# H_bridge.net
KiCad netlist of a schematic drawn in Altium Designer
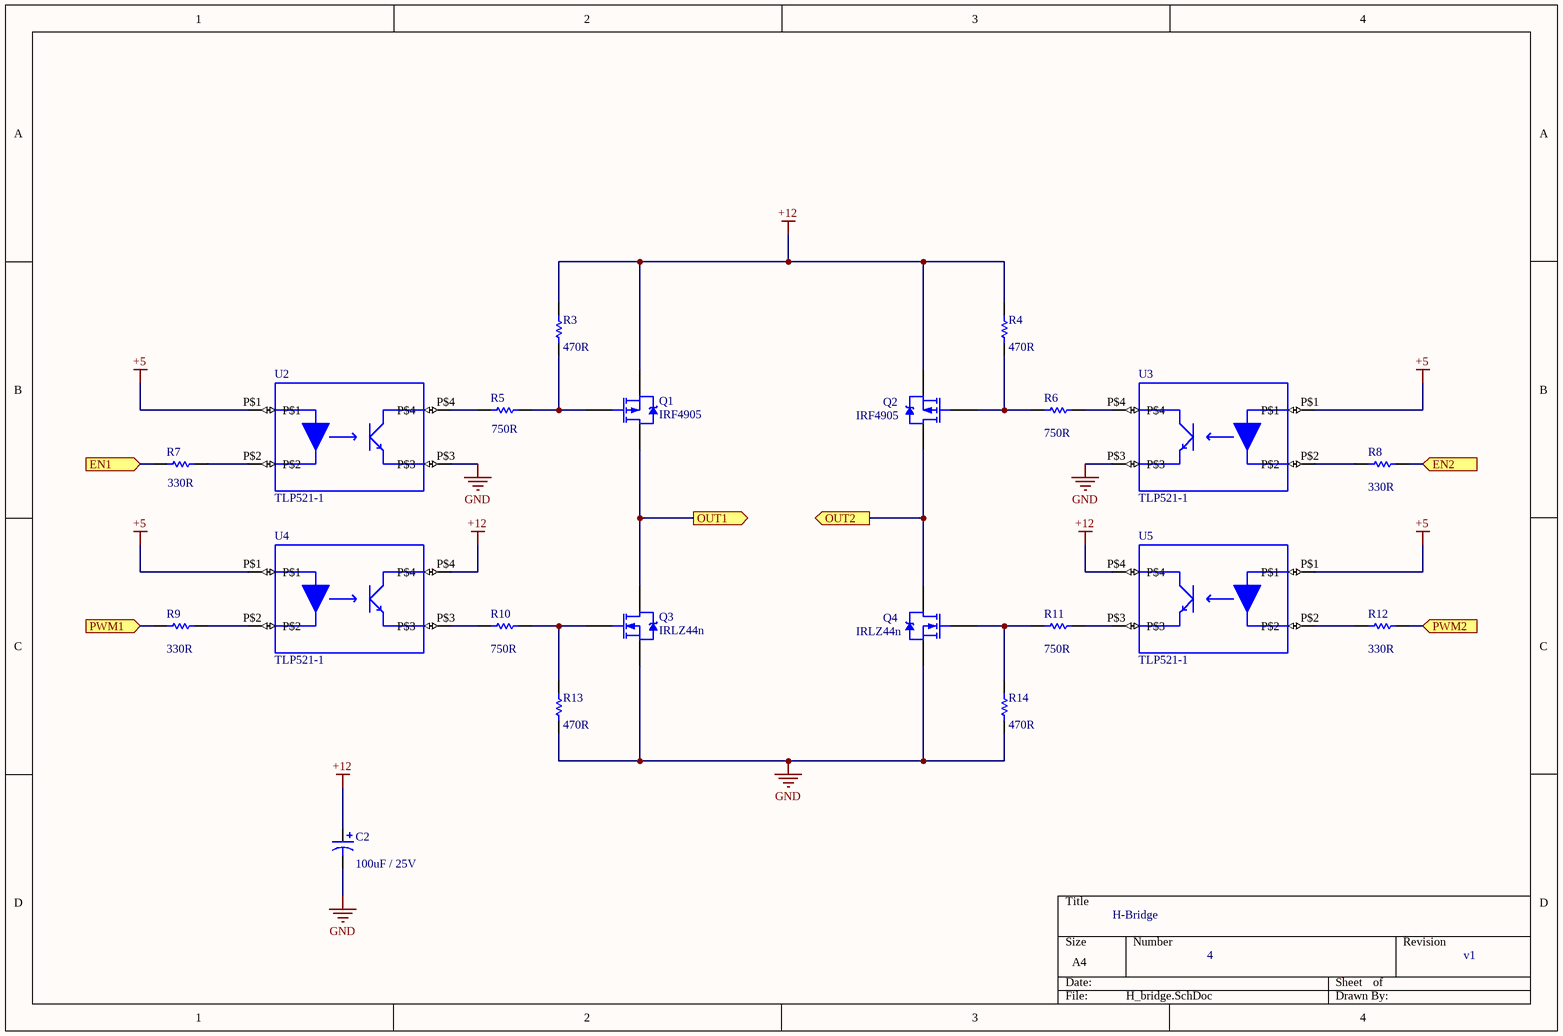
[diagram p0: H_bridge.SchDoc]

(export (version "E")
  (design (tool "Eeschema 10.0.6"))
  (components
    (comp (ref "C2")
      (value "100uF / 25V")
      (footprint "RB7.6-15")
      (description "Polarized Capacitor (Radial)")
      (fields (field (name "Comment") "Cap Pol1") (field (name "PUBLISHER") "Altium Limited"))
      (libsource (lib "Miscellaneous Devices") (part "Cap Pol1"))
    )
    (comp (ref "Q1")
      (value "IRF4905")
      (footprint "TO-220AB")
      (description "P-Channel Power MOSFET")
      (fields (field (name "PUBLISHER") "Altium Limited"))
      (libsource (lib "Miscellaneous Devices") (part "PMOS-2"))
    )
    (comp (ref "Q2")
      (value "IRF4905")
      (footprint "TO-220AB")
      (description "P-Channel Power MOSFET")
      (fields (field (name "PUBLISHER") "Altium Limited"))
      (libsource (lib "Miscellaneous Devices") (part "PMOS-2"))
    )
    (comp (ref "Q3")
      (value "IRLZ44n")
      (footprint "TO-220AB")
      (description "N-Channel Power MOSFET")
      (fields (field (name "PUBLISHER") "Altium Limited"))
      (libsource (lib "Miscellaneous Devices") (part "NMOS-2"))
    )
    (comp (ref "Q4")
      (value "IRLZ44n")
      (footprint "TO-220AB")
      (description "N-Channel Power MOSFET")
      (fields (field (name "PUBLISHER") "Altium Limited"))
      (libsource (lib "Miscellaneous Devices") (part "NMOS-2"))
    )
    (comp (ref "R3")
      (value "470R")
      (footprint "AXIAL-0.3")
      (description "Resistor")
      (fields (field (name "Comment") "Res1") (field (name "PUBLISHER") "Altium Limited"))
      (libsource (lib "Miscellaneous Devices") (part "Res1"))
    )
    (comp (ref "R4")
      (value "470R")
      (footprint "AXIAL-0.3")
      (description "Resistor")
      (fields (field (name "Comment") "Res1") (field (name "PUBLISHER") "Altium Limited"))
      (libsource (lib "Miscellaneous Devices") (part "Res1"))
    )
    (comp (ref "R5")
      (value "750R")
      (footprint "AXIAL-0.3")
      (description "Resistor")
      (fields (field (name "Comment") "Res1") (field (name "PUBLISHER") "Altium Limited"))
      (libsource (lib "Miscellaneous Devices") (part "Res1"))
    )
    (comp (ref "R6")
      (value "750R")
      (footprint "AXIAL-0.3")
      (description "Resistor")
      (fields (field (name "Comment") "Res1") (field (name "PUBLISHER") "Altium Limited"))
      (libsource (lib "Miscellaneous Devices") (part "Res1"))
    )
    (comp (ref "R7")
      (value "330R")
      (footprint "AXIAL-0.3")
      (description "Resistor")
      (fields (field (name "Comment") "Res1") (field (name "PUBLISHER") "Altium Limited"))
      (libsource (lib "Miscellaneous Devices") (part "Res1"))
    )
    (comp (ref "R8")
      (value "330R")
      (footprint "AXIAL-0.3")
      (description "Resistor")
      (fields (field (name "Comment") "Res1") (field (name "PUBLISHER") "Altium Limited"))
      (libsource (lib "Miscellaneous Devices") (part "Res1"))
    )
    (comp (ref "R9")
      (value "330R")
      (footprint "AXIAL-0.3")
      (description "Resistor")
      (fields (field (name "Comment") "Res1") (field (name "PUBLISHER") "Altium Limited"))
      (libsource (lib "Miscellaneous Devices") (part "Res1"))
    )
    (comp (ref "R10")
      (value "750R")
      (footprint "AXIAL-0.3")
      (description "Resistor")
      (fields (field (name "Comment") "Res1") (field (name "PUBLISHER") "Altium Limited"))
      (libsource (lib "Miscellaneous Devices") (part "Res1"))
    )
    (comp (ref "R11")
      (value "750R")
      (footprint "AXIAL-0.3")
      (description "Resistor")
      (fields (field (name "Comment") "Res1") (field (name "PUBLISHER") "Altium Limited"))
      (libsource (lib "Miscellaneous Devices") (part "Res1"))
    )
    (comp (ref "R12")
      (value "330R")
      (footprint "AXIAL-0.3")
      (description "Resistor")
      (fields (field (name "Comment") "Res1") (field (name "PUBLISHER") "Altium Limited"))
      (libsource (lib "Miscellaneous Devices") (part "Res1"))
    )
    (comp (ref "R13")
      (value "470R")
      (footprint "AXIAL-0.3")
      (description "Resistor")
      (fields (field (name "Comment") "Res1") (field (name "PUBLISHER") "Altium Limited"))
      (libsource (lib "Miscellaneous Devices") (part "Res1"))
    )
    (comp (ref "R14")
      (value "470R")
      (footprint "AXIAL-0.3")
      (description "Resistor")
      (fields (field (name "Comment") "Res1") (field (name "PUBLISHER") "Altium Limited"))
      (libsource (lib "Miscellaneous Devices") (part "Res1"))
    )
    (comp (ref "U2")
      (value "TLP521-1")
      (footprint "TLP521-1")
      (description "ICM006")
      (fields (field (name "MF") "Isocom"))
      (libsource (lib "TLP521-1") (part "TLP521-1"))
    )
    (comp (ref "U3")
      (value "TLP521-1")
      (footprint "TLP521-1")
      (description "ICM006")
      (fields (field (name "MF") "Isocom"))
      (libsource (lib "TLP521-1") (part "TLP521-1"))
    )
    (comp (ref "U4")
      (value "TLP521-1")
      (footprint "TLP521-1")
      (description "ICM006")
      (fields (field (name "MF") "Isocom"))
      (libsource (lib "TLP521-1") (part "TLP521-1"))
    )
    (comp (ref "U5")
      (value "TLP521-1")
      (footprint "TLP521-1")
      (description "ICM006")
      (fields (field (name "MF") "Isocom"))
      (libsource (lib "TLP521-1") (part "TLP521-1"))
    )
  )
  (nets
    (net (code "1") (name "+5") (class "Default")
      (node (ref "U2") (pin "P$1") (pinfunction "P$1_P$1") (pintype "bidirectional"))
      (node (ref "U3") (pin "P$1") (pinfunction "P$1_P$1") (pintype "bidirectional"))
      (node (ref "U4") (pin "P$1") (pinfunction "P$1_P$1") (pintype "bidirectional"))
      (node (ref "U5") (pin "P$1") (pinfunction "P$1_P$1") (pintype "bidirectional"))
    )
    (net (code "2") (name "+12") (class "Default")
      (node (ref "C2") (pin "1") (pinfunction "1_1") (pintype "passive"))
      (node (ref "Q1") (pin "3") (pinfunction "S_3") (pintype "passive"))
      (node (ref "Q2") (pin "3") (pinfunction "S_3") (pintype "passive"))
      (node (ref "R3") (pin "2") (pinfunction "2_2") (pintype "passive"))
      (node (ref "R4") (pin "2") (pinfunction "2_2") (pintype "passive"))
      (node (ref "U4") (pin "P$4") (pinfunction "P$4_P$4") (pintype "bidirectional"))
      (node (ref "U5") (pin "P$4") (pinfunction "P$4_P$4") (pintype "bidirectional"))
    )
    (net (code "3") (name "/EN1") (class "Default")
      (node (ref "R7") (pin "1") (pinfunction "1_1") (pintype "passive"))
    )
    (net (code "4") (name "/EN2") (class "Default")
      (node (ref "R8") (pin "1") (pinfunction "1_1") (pintype "passive"))
    )
    (net (code "5") (name "/OUT1") (class "Default")
      (node (ref "Q1") (pin "2") (pinfunction "D_2") (pintype "passive"))
      (node (ref "Q3") (pin "2") (pinfunction "D_2") (pintype "passive"))
    )
    (net (code "6") (name "/OUT2") (class "Default")
      (node (ref "Q2") (pin "2") (pinfunction "D_2") (pintype "passive"))
      (node (ref "Q4") (pin "2") (pinfunction "D_2") (pintype "passive"))
    )
    (net (code "7") (name "/PWM1") (class "Default")
      (node (ref "R9") (pin "2") (pinfunction "2_2") (pintype "passive"))
    )
    (net (code "8") (name "/PWM2") (class "Default")
      (node (ref "R12") (pin "2") (pinfunction "2_2") (pintype "passive"))
    )
    (net (code "9") (name "GND") (class "Default")
      (node (ref "C2") (pin "2") (pinfunction "2_2") (pintype "passive"))
      (node (ref "Q3") (pin "3") (pinfunction "S_3") (pintype "passive"))
      (node (ref "Q4") (pin "3") (pinfunction "S_3") (pintype "passive"))
      (node (ref "R13") (pin "2") (pinfunction "2_2") (pintype "passive"))
      (node (ref "R14") (pin "2") (pinfunction "2_2") (pintype "passive"))
      (node (ref "U2") (pin "P$3") (pinfunction "P$3_P$3") (pintype "bidirectional"))
      (node (ref "U3") (pin "P$3") (pinfunction "P$3_P$3") (pintype "bidirectional"))
    )
    (net (code "10") (name "Net-(Q1-G)") (class "Default")
      (node (ref "Q1") (pin "1") (pinfunction "G_1") (pintype "passive"))
      (node (ref "R3") (pin "1") (pinfunction "1_1") (pintype "passive"))
      (node (ref "R5") (pin "2") (pinfunction "2_2") (pintype "passive"))
    )
    (net (code "11") (name "Net-(Q2-G)") (class "Default")
      (node (ref "Q2") (pin "1") (pinfunction "G_1") (pintype "passive"))
      (node (ref "R4") (pin "1") (pinfunction "1_1") (pintype "passive"))
      (node (ref "R6") (pin "2") (pinfunction "2_2") (pintype "passive"))
    )
    (net (code "12") (name "Net-(Q3-G)") (class "Default")
      (node (ref "Q3") (pin "1") (pinfunction "G_1") (pintype "passive"))
      (node (ref "R10") (pin "1") (pinfunction "1_1") (pintype "passive"))
      (node (ref "R13") (pin "1") (pinfunction "1_1") (pintype "passive"))
    )
    (net (code "13") (name "Net-(Q4-G)") (class "Default")
      (node (ref "Q4") (pin "1") (pinfunction "G_1") (pintype "passive"))
      (node (ref "R11") (pin "1") (pinfunction "1_1") (pintype "passive"))
      (node (ref "R14") (pin "1") (pinfunction "1_1") (pintype "passive"))
    )
    (net (code "14") (name "Net-(R5-Pad1)") (class "Default")
      (node (ref "R5") (pin "1") (pinfunction "1_1") (pintype "passive"))
      (node (ref "U2") (pin "P$4") (pinfunction "P$4_P$4") (pintype "bidirectional"))
    )
    (net (code "15") (name "Net-(R6-Pad1)") (class "Default")
      (node (ref "R6") (pin "1") (pinfunction "1_1") (pintype "passive"))
      (node (ref "U3") (pin "P$4") (pinfunction "P$4_P$4") (pintype "bidirectional"))
    )
    (net (code "16") (name "Net-(R7-Pad2)") (class "Default")
      (node (ref "R7") (pin "2") (pinfunction "2_2") (pintype "passive"))
      (node (ref "U2") (pin "P$2") (pinfunction "P$2_P$2") (pintype "bidirectional"))
    )
    (net (code "17") (name "Net-(R8-Pad2)") (class "Default")
      (node (ref "R8") (pin "2") (pinfunction "2_2") (pintype "passive"))
      (node (ref "U3") (pin "P$2") (pinfunction "P$2_P$2") (pintype "bidirectional"))
    )
    (net (code "18") (name "Net-(R9-Pad1)") (class "Default")
      (node (ref "R9") (pin "1") (pinfunction "1_1") (pintype "passive"))
      (node (ref "U4") (pin "P$2") (pinfunction "P$2_P$2") (pintype "bidirectional"))
    )
    (net (code "19") (name "Net-(R10-Pad2)") (class "Default")
      (node (ref "R10") (pin "2") (pinfunction "2_2") (pintype "passive"))
      (node (ref "U4") (pin "P$3") (pinfunction "P$3_P$3") (pintype "bidirectional"))
    )
    (net (code "20") (name "Net-(R11-Pad2)") (class "Default")
      (node (ref "R11") (pin "2") (pinfunction "2_2") (pintype "passive"))
      (node (ref "U5") (pin "P$3") (pinfunction "P$3_P$3") (pintype "bidirectional"))
    )
    (net (code "21") (name "Net-(R12-Pad1)") (class "Default")
      (node (ref "R12") (pin "1") (pinfunction "1_1") (pintype "passive"))
      (node (ref "U5") (pin "P$2") (pinfunction "P$2_P$2") (pintype "bidirectional"))
    )
  )
)
